# semafor-b.net
KiCad netlist of a schematic drawn in EAGLE
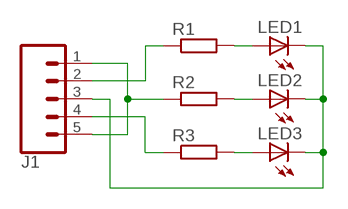
[diagram p0: schematic, sheet 1]

(export (version "E")
  (design (tool "Eeschema 10.0.6"))
  (components
    (comp (ref "J1")
      (value "CONN_05NO_SILK")
      (footprint "eagle-import:1X05_NO_SILK")
      (libsource (lib "eagle-import") (part "CONN_05NO_SILK"))
    )
    (comp (ref "LED1")
      (value "LED5MM")
      (footprint "eagle-import:LED5MM")
      (libsource (lib "eagle-import") (part "LED5MM"))
    )
    (comp (ref "LED2")
      (value "LED5MM")
      (footprint "eagle-import:LED5MM")
      (libsource (lib "eagle-import") (part "LED5MM"))
    )
    (comp (ref "LED3")
      (value "LED5MM")
      (footprint "eagle-import:LED5MM")
      (libsource (lib "eagle-import") (part "LED5MM"))
    )
    (comp (ref "R1")
      (value "R-EU_0207/7")
      (footprint "eagle-import:0207_7")
      (libsource (lib "eagle-import") (part "R-EU_0207/7"))
    )
    (comp (ref "R2")
      (value "R-EU_0207/7")
      (footprint "eagle-import:0207_7")
      (libsource (lib "eagle-import") (part "R-EU_0207/7"))
    )
    (comp (ref "R3")
      (value "R-EU_0207/7")
      (footprint "eagle-import:0207_7")
      (libsource (lib "eagle-import") (part "R-EU_0207/7"))
    )
  )
  (nets
    (net (code "1") (name "Net-(J1-Pad1)") (class "Default")
      (node (ref "J1") (pin "1") (pinfunction "1_1") (pintype "passive"))
      (node (ref "J1") (pin "5") (pinfunction "5_5") (pintype "passive"))
      (node (ref "R2") (pin "1") (pinfunction "1_1") (pintype "passive"))
    )
    (net (code "2") (name "Net-(J1-Pad2)") (class "Default")
      (node (ref "J1") (pin "2") (pinfunction "2_2") (pintype "passive"))
      (node (ref "R1") (pin "1") (pinfunction "1_1") (pintype "passive"))
    )
    (net (code "3") (name "Net-(J1-Pad4)") (class "Default")
      (node (ref "J1") (pin "4") (pinfunction "4_4") (pintype "passive"))
      (node (ref "R3") (pin "1") (pinfunction "1_1") (pintype "passive"))
    )
    (net (code "4") (name "Net-(LED1-C)") (class "Default")
      (node (ref "J1") (pin "3") (pinfunction "3_3") (pintype "passive"))
      (node (ref "LED1") (pin "K") (pinfunction "C_K") (pintype "passive"))
      (node (ref "LED2") (pin "K") (pinfunction "C_K") (pintype "passive"))
      (node (ref "LED3") (pin "K") (pinfunction "C_K") (pintype "passive"))
    )
    (net (code "5") (name "Net-(LED1-PadA)") (class "Default")
      (node (ref "LED1") (pin "A") (pinfunction "A_A") (pintype "passive"))
      (node (ref "R1") (pin "2") (pinfunction "2_2") (pintype "passive"))
    )
    (net (code "6") (name "Net-(LED2-PadA)") (class "Default")
      (node (ref "LED2") (pin "A") (pinfunction "A_A") (pintype "passive"))
      (node (ref "R2") (pin "2") (pinfunction "2_2") (pintype "passive"))
    )
    (net (code "7") (name "Net-(LED3-PadA)") (class "Default")
      (node (ref "LED3") (pin "A") (pinfunction "A_A") (pintype "passive"))
      (node (ref "R3") (pin "2") (pinfunction "2_2") (pintype "passive"))
    )
  )
)
